# TLC4LED.net
KiCad netlist of a schematic drawn in EAGLE
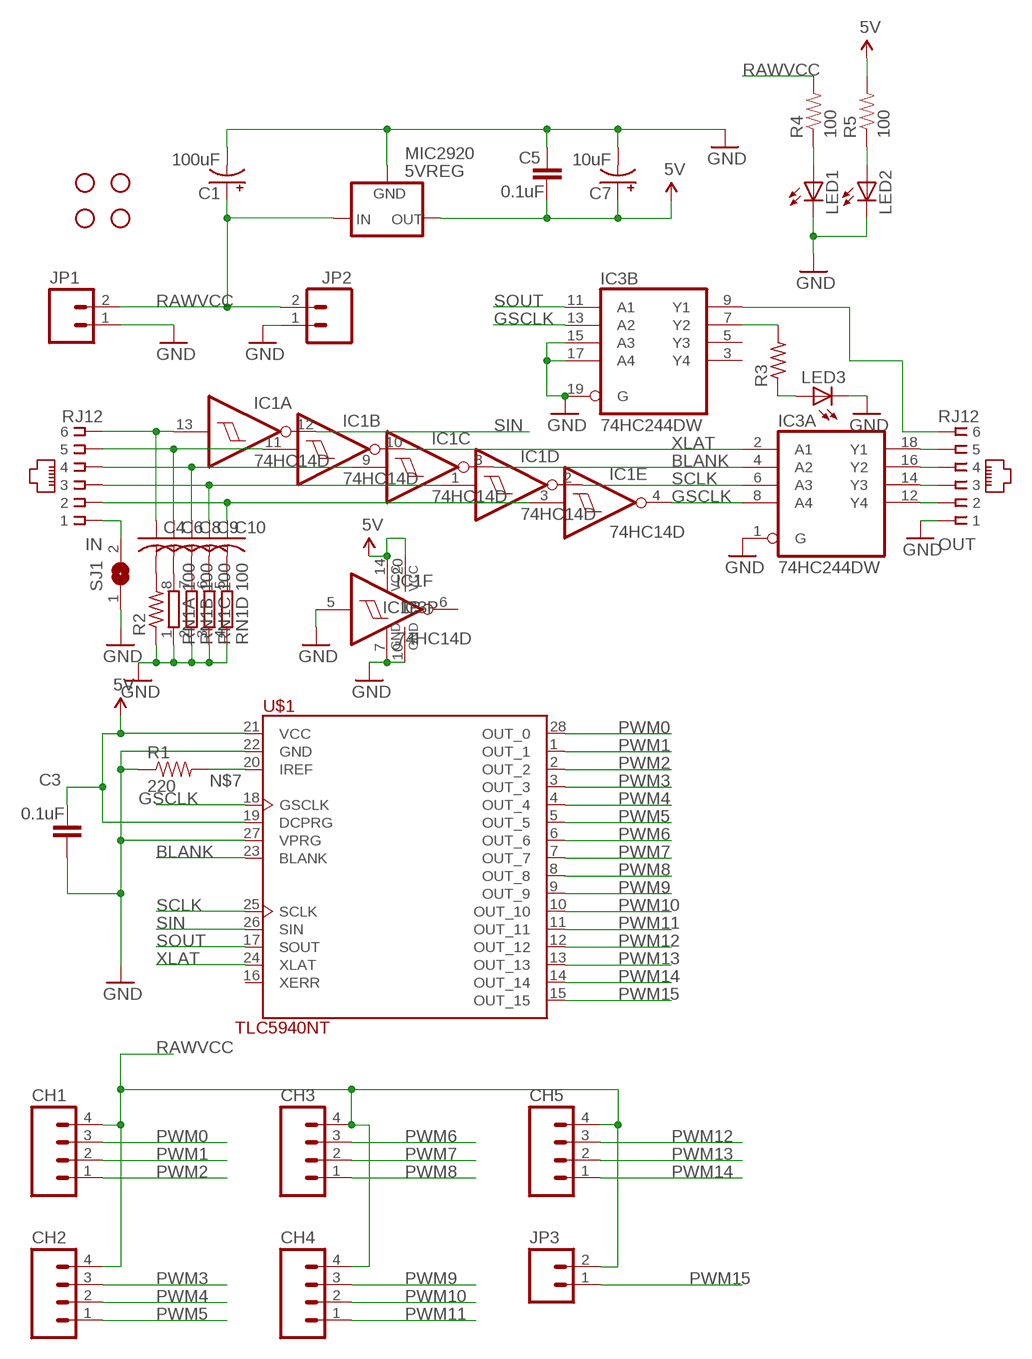
[diagram p0: schematic, sheet 1]

(export (version "E")
  (design (tool "Eeschema 10.0.6"))
  (components
    (comp (ref "5VREG")
      (value "MIC2920")
      (footprint "eagle-import:SOT223")
      (libsource (lib "eagle-import") (part "V_REG_MIC2920"))
    )
    (comp (ref "C1")
      (value "100uF")
      (footprint "eagle-import:PANASONIC_D")
      (libsource (lib "eagle-import") (part "CAP_POLD"))
    )
    (comp (ref "C3")
      (value "0.1uF")
      (footprint "eagle-import:0805")
      (libsource (lib "eagle-import") (part "CAP0805"))
    )
    (comp (ref "C4")
      (value "C-US025-025X050")
      (footprint "eagle-import:C025-025X050")
      (libsource (lib "eagle-import") (part "C-US025-025X050"))
    )
    (comp (ref "C5")
      (value "0.1uF")
      (footprint "eagle-import:0805")
      (libsource (lib "eagle-import") (part "CAP0805"))
    )
    (comp (ref "C6")
      (value "C-US025-025X050")
      (footprint "eagle-import:C025-025X050")
      (libsource (lib "eagle-import") (part "C-US025-025X050"))
    )
    (comp (ref "C7")
      (value "10uF")
      (footprint "eagle-import:EIA3216")
      (libsource (lib "eagle-import") (part "CAP_POL1206"))
    )
    (comp (ref "C8")
      (value "C-US025-025X050")
      (footprint "eagle-import:C025-025X050")
      (libsource (lib "eagle-import") (part "C-US025-025X050"))
    )
    (comp (ref "C9")
      (value "C-US025-025X050")
      (footprint "eagle-import:C025-025X050")
      (libsource (lib "eagle-import") (part "C-US025-025X050"))
    )
    (comp (ref "C10")
      (value "C-US025-025X050")
      (footprint "eagle-import:C025-025X050")
      (libsource (lib "eagle-import") (part "C-US025-025X050"))
    )
    (comp (ref "CH1")
      (value "M04SCREW")
      (footprint "eagle-import:SCREWTERMINAL-3.5MM-4")
      (libsource (lib "eagle-import") (part "M04SCREW"))
    )
    (comp (ref "CH2")
      (value "M04SCREW")
      (footprint "eagle-import:SCREWTERMINAL-3.5MM-4")
      (libsource (lib "eagle-import") (part "M04SCREW"))
    )
    (comp (ref "CH3")
      (value "M04SCREW")
      (footprint "eagle-import:SCREWTERMINAL-3.5MM-4")
      (libsource (lib "eagle-import") (part "M04SCREW"))
    )
    (comp (ref "CH4")
      (value "M04SCREW")
      (footprint "eagle-import:SCREWTERMINAL-3.5MM-4")
      (libsource (lib "eagle-import") (part "M04SCREW"))
    )
    (comp (ref "CH5")
      (value "M04SCREW")
      (footprint "eagle-import:SCREWTERMINAL-3.5MM-4")
      (libsource (lib "eagle-import") (part "M04SCREW"))
    )
    (comp (ref "IC1")
      (value "74HC14D")
      (footprint "eagle-import:SO14")
      (libsource (lib "eagle-import") (part "7414DHC"))
    )
    (comp (ref "IC3")
      (value "74HC244DW")
      (footprint "eagle-import:SO20W")
      (libsource (lib "eagle-import") (part "74244DWHC"))
    )
    (comp (ref "IN")
      (value "RJ12")
      (footprint "eagle-import:RJ11-NO_SHIELD")
      (fields (field (name "MF") "TYCO ELECTRONICS") (field (name "MPN") "RJ11-6L-B"))
      (libsource (lib "eagle-import") (part "RJ11-6L-B"))
    )
    (comp (ref "JP1")
      (value "M023.5MM")
      (footprint "eagle-import:SCREWTERMINAL-3.5MM-2")
      (libsource (lib "eagle-import") (part "M023.5MM"))
    )
    (comp (ref "JP2")
      (value "M023.5MM")
      (footprint "eagle-import:SCREWTERMINAL-3.5MM-2")
      (libsource (lib "eagle-import") (part "M023.5MM"))
    )
    (comp (ref "JP3")
      (value "M023.5MM")
      (footprint "eagle-import:SCREWTERMINAL-3.5MM-2")
      (libsource (lib "eagle-import") (part "M023.5MM"))
    )
    (comp (ref "JP4")
      (value "STAND-OFF")
      (footprint "eagle-import:STAND-OFF")
      (libsource (lib "eagle-import") (part "STAND-OFF"))
    )
    (comp (ref "JP5")
      (value "STAND-OFF")
      (footprint "eagle-import:STAND-OFF")
      (libsource (lib "eagle-import") (part "STAND-OFF"))
    )
    (comp (ref "JP6")
      (value "STAND-OFF")
      (footprint "eagle-import:STAND-OFF")
      (libsource (lib "eagle-import") (part "STAND-OFF"))
    )
    (comp (ref "JP7")
      (value "STAND-OFF")
      (footprint "eagle-import:STAND-OFF")
      (libsource (lib "eagle-import") (part "STAND-OFF"))
    )
    (comp (ref "LED1")
      (value "LEDCHIPLED_0805")
      (footprint "eagle-import:CHIPLED_0805")
      (libsource (lib "eagle-import") (part "LEDCHIPLED_0805"))
    )
    (comp (ref "LED2")
      (value "LEDCHIPLED_0805")
      (footprint "eagle-import:CHIPLED_0805")
      (libsource (lib "eagle-import") (part "LEDCHIPLED_0805"))
    )
    (comp (ref "LED3")
      (value "LEDCHIPLED_0805")
      (footprint "eagle-import:CHIPLED_0805")
      (libsource (lib "eagle-import") (part "LEDCHIPLED_0805"))
    )
    (comp (ref "OUT")
      (value "RJ12")
      (footprint "eagle-import:RJ11-NO_SHIELD")
      (fields
        (field (name "MF") "TYCO ELECTRONICS")
        (field (name "MPN") "RJ11-6L-B")
        (field (name "MF_1") "TYCO ELECTRONICS")
        (field (name "MPN_1") "RJ11-6L-B")
        (field (name "OC_FARNELL") "unknown")
        (field (name "OC_NEWARK") "52K3613")
      )
      (libsource (lib "eagle-import") (part "RJ11-6L-B"))
    )
    (comp (ref "R1")
      (value "220")
      (footprint "eagle-import:0805")
      (libsource (lib "eagle-import") (part "RESISTOR0805-RES"))
    )
    (comp (ref "R2")
      (value "R-US_R0805")
      (footprint "eagle-import:R0805")
      (libsource (lib "eagle-import") (part "R-US_R0805"))
    )
    (comp (ref "R3")
      (value "R-US_R0805")
      (footprint "eagle-import:R0805")
      (libsource (lib "eagle-import") (part "R-US_R0805"))
    )
    (comp (ref "R4")
      (value "100")
      (footprint "eagle-import:0805")
      (libsource (lib "eagle-import") (part "RESISTOR0805-RES"))
    )
    (comp (ref "R5")
      (value "100")
      (footprint "eagle-import:0805")
      (libsource (lib "eagle-import") (part "RESISTOR0805-RES"))
    )
    (comp (ref "RN1")
      (value "100")
      (footprint "eagle-import:EXBS8V")
      (libsource (lib "eagle-import") (part "4R-NEXBS8V"))
    )
    (comp (ref "SJ1") (value "SJ") (footprint "eagle-import:SJ") (libsource (lib "eagle-import") (part "SJ")))
    (comp (ref "U$1")
      (value "TLC5940NT")
      (footprint "eagle-import:DIP-28")
      (libsource (lib "eagle-import") (part "TLC5940NT"))
    )
  )
  (nets
    (net (code "1") (name "/BLANK") (class "Default")
      (node (ref "IC1") (pin "8") (pinfunction "O_8") (pintype "output"))
      (node (ref "IC3") (pin "4") (pinfunction "A2_4") (pintype "input"))
      (node (ref "U$1") (pin "23") (pinfunction "BLANK_23") (pintype "input"))
    )
    (net (code "2") (name "/GSCLK") (class "Default")
      (node (ref "IC1") (pin "4") (pinfunction "O_4") (pintype "output"))
      (node (ref "IC3") (pin "13") (pinfunction "A2_13") (pintype "input"))
      (node (ref "IC3") (pin "8") (pinfunction "A4_8") (pintype "input"))
      (node (ref "U$1") (pin "18") (pinfunction "GSCLK_18") (pintype "input"))
    )
    (net (code "3") (name "/N$7") (class "Default")
      (node (ref "R1") (pin "2") (pinfunction "2_2") (pintype "passive"))
      (node (ref "U$1") (pin "20") (pinfunction "IREF_20") (pintype "power_in"))
    )
    (net (code "4") (name "/PWM0") (class "Default")
      (node (ref "CH1") (pin "3") (pinfunction "3_3") (pintype "passive"))
      (node (ref "U$1") (pin "28") (pinfunction "OUT_0_28") (pintype "output"))
    )
    (net (code "5") (name "/PWM1") (class "Default")
      (node (ref "CH1") (pin "2") (pinfunction "2_2") (pintype "passive"))
      (node (ref "U$1") (pin "1") (pinfunction "OUT_1_1") (pintype "output"))
    )
    (net (code "6") (name "/PWM2") (class "Default")
      (node (ref "CH1") (pin "1") (pinfunction "1_1") (pintype "passive"))
      (node (ref "U$1") (pin "2") (pinfunction "OUT_2_2") (pintype "output"))
    )
    (net (code "7") (name "/PWM3") (class "Default")
      (node (ref "CH2") (pin "3") (pinfunction "3_3") (pintype "passive"))
      (node (ref "U$1") (pin "3") (pinfunction "OUT_3_3") (pintype "output"))
    )
    (net (code "8") (name "/PWM4") (class "Default")
      (node (ref "CH2") (pin "2") (pinfunction "2_2") (pintype "passive"))
      (node (ref "U$1") (pin "4") (pinfunction "OUT_4_4") (pintype "output"))
    )
    (net (code "9") (name "/PWM5") (class "Default")
      (node (ref "CH2") (pin "1") (pinfunction "1_1") (pintype "passive"))
      (node (ref "U$1") (pin "5") (pinfunction "OUT_5_5") (pintype "output"))
    )
    (net (code "10") (name "/PWM6") (class "Default")
      (node (ref "CH3") (pin "3") (pinfunction "3_3") (pintype "passive"))
      (node (ref "U$1") (pin "6") (pinfunction "OUT_6_6") (pintype "output"))
    )
    (net (code "11") (name "/PWM7") (class "Default")
      (node (ref "CH3") (pin "2") (pinfunction "2_2") (pintype "passive"))
      (node (ref "U$1") (pin "7") (pinfunction "OUT_7_7") (pintype "output"))
    )
    (net (code "12") (name "/PWM8") (class "Default")
      (node (ref "CH3") (pin "1") (pinfunction "1_1") (pintype "passive"))
      (node (ref "U$1") (pin "8") (pinfunction "OUT_8_8") (pintype "output"))
    )
    (net (code "13") (name "/PWM9") (class "Default")
      (node (ref "CH4") (pin "3") (pinfunction "3_3") (pintype "passive"))
      (node (ref "U$1") (pin "9") (pinfunction "OUT_9_9") (pintype "output"))
    )
    (net (code "14") (name "/PWM10") (class "Default")
      (node (ref "CH4") (pin "2") (pinfunction "2_2") (pintype "passive"))
      (node (ref "U$1") (pin "10") (pinfunction "OUT_10_10") (pintype "output"))
    )
    (net (code "15") (name "/PWM11") (class "Default")
      (node (ref "CH4") (pin "1") (pinfunction "1_1") (pintype "passive"))
      (node (ref "U$1") (pin "11") (pinfunction "OUT_11_11") (pintype "output"))
    )
    (net (code "16") (name "/PWM12") (class "Default")
      (node (ref "CH5") (pin "3") (pinfunction "3_3") (pintype "passive"))
      (node (ref "U$1") (pin "12") (pinfunction "OUT_12_12") (pintype "output"))
    )
    (net (code "17") (name "/PWM13") (class "Default")
      (node (ref "CH5") (pin "2") (pinfunction "2_2") (pintype "passive"))
      (node (ref "U$1") (pin "13") (pinfunction "OUT_13_13") (pintype "output"))
    )
    (net (code "18") (name "/PWM14") (class "Default")
      (node (ref "CH5") (pin "1") (pinfunction "1_1") (pintype "passive"))
      (node (ref "U$1") (pin "14") (pinfunction "OUT_14_14") (pintype "output"))
    )
    (net (code "19") (name "/PWM15") (class "Default")
      (node (ref "JP3") (pin "1") (pinfunction "1_1") (pintype "passive"))
      (node (ref "U$1") (pin "15") (pinfunction "OUT_15_15") (pintype "output"))
    )
    (net (code "20") (name "/RAWVCC") (class "Default")
      (node (ref "5VREG") (pin "1") (pinfunction "IN_1") (pintype "input"))
      (node (ref "C1") (pin "+") (pinfunction "+_+") (pintype "passive"))
      (node (ref "CH1") (pin "4") (pinfunction "4_4") (pintype "passive"))
      (node (ref "CH2") (pin "4") (pinfunction "4_4") (pintype "passive"))
      (node (ref "CH3") (pin "4") (pinfunction "4_4") (pintype "passive"))
      (node (ref "CH4") (pin "4") (pinfunction "4_4") (pintype "passive"))
      (node (ref "CH5") (pin "4") (pinfunction "4_4") (pintype "passive"))
      (node (ref "JP1") (pin "2") (pinfunction "2_2") (pintype "passive"))
      (node (ref "JP2") (pin "2") (pinfunction "2_2") (pintype "passive"))
      (node (ref "JP3") (pin "2") (pinfunction "2_2") (pintype "passive"))
      (node (ref "R4") (pin "2") (pinfunction "2_2") (pintype "passive"))
    )
    (net (code "21") (name "/SCLK") (class "Default")
      (node (ref "IC1") (pin "2") (pinfunction "O_2") (pintype "output"))
      (node (ref "IC3") (pin "6") (pinfunction "A3_6") (pintype "input"))
      (node (ref "U$1") (pin "25") (pinfunction "SCLK_25") (pintype "input"))
    )
    (net (code "22") (name "/SIN") (class "Default")
      (node (ref "IC1") (pin "12") (pinfunction "O_12") (pintype "output"))
      (node (ref "U$1") (pin "26") (pinfunction "SIN_26") (pintype "input"))
    )
    (net (code "23") (name "/SOUT") (class "Default")
      (node (ref "IC3") (pin "11") (pinfunction "A1_11") (pintype "input"))
      (node (ref "U$1") (pin "17") (pinfunction "SOUT_17") (pintype "output"))
    )
    (net (code "24") (name "/XLAT") (class "Default")
      (node (ref "IC1") (pin "10") (pinfunction "O_10") (pintype "output"))
      (node (ref "IC3") (pin "2") (pinfunction "A1_2") (pintype "input"))
      (node (ref "U$1") (pin "24") (pinfunction "XLAT_24") (pintype "input"))
    )
    (net (code "25") (name "5V") (class "Default")
      (node (ref "5VREG") (pin "3") (pinfunction "OUT_3") (pintype "output"))
      (node (ref "C3") (pin "2") (pinfunction "2_2") (pintype "passive"))
      (node (ref "C5") (pin "1") (pinfunction "1_1") (pintype "passive"))
      (node (ref "C7") (pin "A") (pinfunction "+_A") (pintype "passive"))
      (node (ref "IC1") (pin "14") (pinfunction "VCC_14") (pintype "power_in"))
      (node (ref "IC3") (pin "20") (pinfunction "VCC_20") (pintype "power_in"))
      (node (ref "R5") (pin "2") (pinfunction "2_2") (pintype "passive"))
      (node (ref "U$1") (pin "19") (pinfunction "DCPRG_19") (pintype "input"))
      (node (ref "U$1") (pin "21") (pinfunction "VCC_21") (pintype "power_in"))
    )
    (net (code "26") (name "GND") (class "Default")
      (node (ref "5VREG") (pin "2") (pinfunction "GND_2") (pintype "input"))
      (node (ref "C1") (pin "-") (pinfunction "-_-") (pintype "passive"))
      (node (ref "C3") (pin "1") (pinfunction "1_1") (pintype "passive"))
      (node (ref "C5") (pin "2") (pinfunction "2_2") (pintype "passive"))
      (node (ref "C7") (pin "C") (pinfunction "-_C") (pintype "passive"))
      (node (ref "IC1") (pin "5") (pinfunction "I_5") (pintype "input"))
      (node (ref "IC1") (pin "7") (pinfunction "GND_7") (pintype "power_in"))
      (node (ref "IC3") (pin "1") (pinfunction "G_1") (pintype "input"))
      (node (ref "IC3") (pin "10") (pinfunction "GND_10") (pintype "power_in"))
      (node (ref "IC3") (pin "15") (pinfunction "A3_15") (pintype "input"))
      (node (ref "IC3") (pin "17") (pinfunction "A4_17") (pintype "input"))
      (node (ref "IC3") (pin "19") (pinfunction "G_19") (pintype "input"))
      (node (ref "JP1") (pin "1") (pinfunction "1_1") (pintype "passive"))
      (node (ref "JP2") (pin "1") (pinfunction "1_1") (pintype "passive"))
      (node (ref "LED1") (pin "C") (pinfunction "C_C") (pintype "passive"))
      (node (ref "LED2") (pin "C") (pinfunction "C_C") (pintype "passive"))
      (node (ref "LED3") (pin "C") (pinfunction "C_C") (pintype "passive"))
      (node (ref "OUT") (pin "1") (pinfunction "1_1") (pintype "passive"))
      (node (ref "R1") (pin "1") (pinfunction "1_1") (pintype "passive"))
      (node (ref "R2") (pin "1") (pinfunction "1_1") (pintype "passive"))
      (node (ref "RN1") (pin "1") (pinfunction "1_1") (pintype "passive"))
      (node (ref "RN1") (pin "2") (pinfunction "1_2") (pintype "passive"))
      (node (ref "RN1") (pin "3") (pinfunction "1_3") (pintype "passive"))
      (node (ref "RN1") (pin "4") (pinfunction "1_4") (pintype "passive"))
      (node (ref "SJ1") (pin "1") (pinfunction "1_1") (pintype "passive"))
      (node (ref "U$1") (pin "22") (pinfunction "GND_22") (pintype "power_in"))
      (node (ref "U$1") (pin "27") (pinfunction "VPRG_27") (pintype "input"))
    )
    (net (code "27") (name "Net-(C4-Pad2)") (class "Default")
      (node (ref "C4") (pin "2") (pinfunction "2_2") (pintype "passive"))
      (node (ref "R2") (pin "2") (pinfunction "2_2") (pintype "passive"))
    )
    (net (code "28") (name "Net-(IC1A-I)") (class "Default")
      (node (ref "C4") (pin "1") (pinfunction "1_1") (pintype "passive"))
      (node (ref "IC1") (pin "13") (pinfunction "I_13") (pintype "input"))
      (node (ref "IN") (pin "6") (pinfunction "6_6") (pintype "passive"))
    )
    (net (code "29") (name "Net-(IC1B-I)") (class "Default")
      (node (ref "C6") (pin "1") (pinfunction "1_1") (pintype "passive"))
      (node (ref "IC1") (pin "11") (pinfunction "I_11") (pintype "input"))
      (node (ref "IN") (pin "5") (pinfunction "5_5") (pintype "passive"))
    )
    (net (code "30") (name "Net-(IC1C-I)") (class "Default")
      (node (ref "C8") (pin "1") (pinfunction "1_1") (pintype "passive"))
      (node (ref "IC1") (pin "9") (pinfunction "I_9") (pintype "input"))
      (node (ref "IN") (pin "4") (pinfunction "4_4") (pintype "passive"))
    )
    (net (code "31") (name "Net-(IC1D-I)") (class "Default")
      (node (ref "C9") (pin "1") (pinfunction "1_1") (pintype "passive"))
      (node (ref "IC1") (pin "1") (pinfunction "I_1") (pintype "input"))
      (node (ref "IN") (pin "3") (pinfunction "3_3") (pintype "passive"))
    )
    (net (code "32") (name "Net-(IC1E-I)") (class "Default")
      (node (ref "C10") (pin "1") (pinfunction "1_1") (pintype "passive"))
      (node (ref "IC1") (pin "3") (pinfunction "I_3") (pintype "input"))
      (node (ref "IN") (pin "2") (pinfunction "2_2") (pintype "passive"))
    )
    (net (code "33") (name "Net-(IC3A-Y1)") (class "Default")
      (node (ref "IC3") (pin "18") (pinfunction "Y1_18") (pintype "tri_state"))
      (node (ref "OUT") (pin "5") (pinfunction "5_5") (pintype "passive"))
    )
    (net (code "34") (name "Net-(IC3A-Y2)") (class "Default")
      (node (ref "IC3") (pin "16") (pinfunction "Y2_16") (pintype "tri_state"))
      (node (ref "OUT") (pin "4") (pinfunction "4_4") (pintype "passive"))
    )
    (net (code "35") (name "Net-(IC3A-Y3)") (class "Default")
      (node (ref "IC3") (pin "14") (pinfunction "Y3_14") (pintype "tri_state"))
      (node (ref "OUT") (pin "3") (pinfunction "3_3") (pintype "passive"))
    )
    (net (code "36") (name "Net-(IC3A-Y4)") (class "Default")
      (node (ref "IC3") (pin "12") (pinfunction "Y4_12") (pintype "tri_state"))
      (node (ref "OUT") (pin "2") (pinfunction "2_2") (pintype "passive"))
    )
    (net (code "37") (name "Net-(IC3B-Y1)") (class "Default")
      (node (ref "IC3") (pin "9") (pinfunction "Y1_9") (pintype "tri_state"))
      (node (ref "OUT") (pin "6") (pinfunction "6_6") (pintype "passive"))
    )
    (net (code "38") (name "Net-(IC3B-Y2)") (class "Default")
      (node (ref "IC3") (pin "7") (pinfunction "Y2_7") (pintype "tri_state"))
      (node (ref "R3") (pin "2") (pinfunction "2_2") (pintype "passive"))
    )
    (net (code "39") (name "Net-(IN-Pad1)") (class "Default")
      (node (ref "IN") (pin "1") (pinfunction "1_1") (pintype "passive"))
      (node (ref "SJ1") (pin "2") (pinfunction "2_2") (pintype "passive"))
    )
    (net (code "40") (name "Net-(LED1-PadA)") (class "Default")
      (node (ref "LED1") (pin "A") (pinfunction "A_A") (pintype "passive"))
      (node (ref "R4") (pin "1") (pinfunction "1_1") (pintype "passive"))
    )
    (net (code "41") (name "Net-(LED2-PadA)") (class "Default")
      (node (ref "LED2") (pin "A") (pinfunction "A_A") (pintype "passive"))
      (node (ref "R5") (pin "1") (pinfunction "1_1") (pintype "passive"))
    )
    (net (code "42") (name "Net-(LED3-PadA)") (class "Default")
      (node (ref "LED3") (pin "A") (pinfunction "A_A") (pintype "passive"))
      (node (ref "R3") (pin "1") (pinfunction "1_1") (pintype "passive"))
    )
    (net (code "43") (name "Net-(RN1A-2)") (class "Default")
      (node (ref "C6") (pin "2") (pinfunction "2_2") (pintype "passive"))
      (node (ref "RN1") (pin "8") (pinfunction "2_8") (pintype "passive"))
    )
    (net (code "44") (name "Net-(RN1B-2)") (class "Default")
      (node (ref "C8") (pin "2") (pinfunction "2_2") (pintype "passive"))
      (node (ref "RN1") (pin "7") (pinfunction "2_7") (pintype "passive"))
    )
    (net (code "45") (name "Net-(RN1C-2)") (class "Default")
      (node (ref "C9") (pin "2") (pinfunction "2_2") (pintype "passive"))
      (node (ref "RN1") (pin "6") (pinfunction "2_6") (pintype "passive"))
    )
    (net (code "46") (name "Net-(RN1D-2)") (class "Default")
      (node (ref "C10") (pin "2") (pinfunction "2_2") (pintype "passive"))
      (node (ref "RN1") (pin "5") (pinfunction "2_5") (pintype "passive"))
    )
    (net (code "47") (name "unconnected-(IC1F-O-Pad6)") (class "Default")
      (node (ref "IC1") (pin "6") (pinfunction "O_6") (pintype "output"))
    )
    (net (code "48") (name "unconnected-(IC3B-Y3-Pad5)") (class "Default")
      (node (ref "IC3") (pin "5") (pinfunction "Y3_5") (pintype "tri_state"))
    )
    (net (code "49") (name "unconnected-(IC3B-Y4-Pad3)") (class "Default")
      (node (ref "IC3") (pin "3") (pinfunction "Y4_3") (pintype "tri_state"))
    )
    (net (code "50") (name "unconnected-(U$1-XERR-Pad16)") (class "Default")
      (node (ref "U$1") (pin "16") (pinfunction "XERR_16") (pintype "output"))
    )
  )
)
